# SCH_Driver_RL.net
KiCad netlist of a schematic drawn in Altium Designer
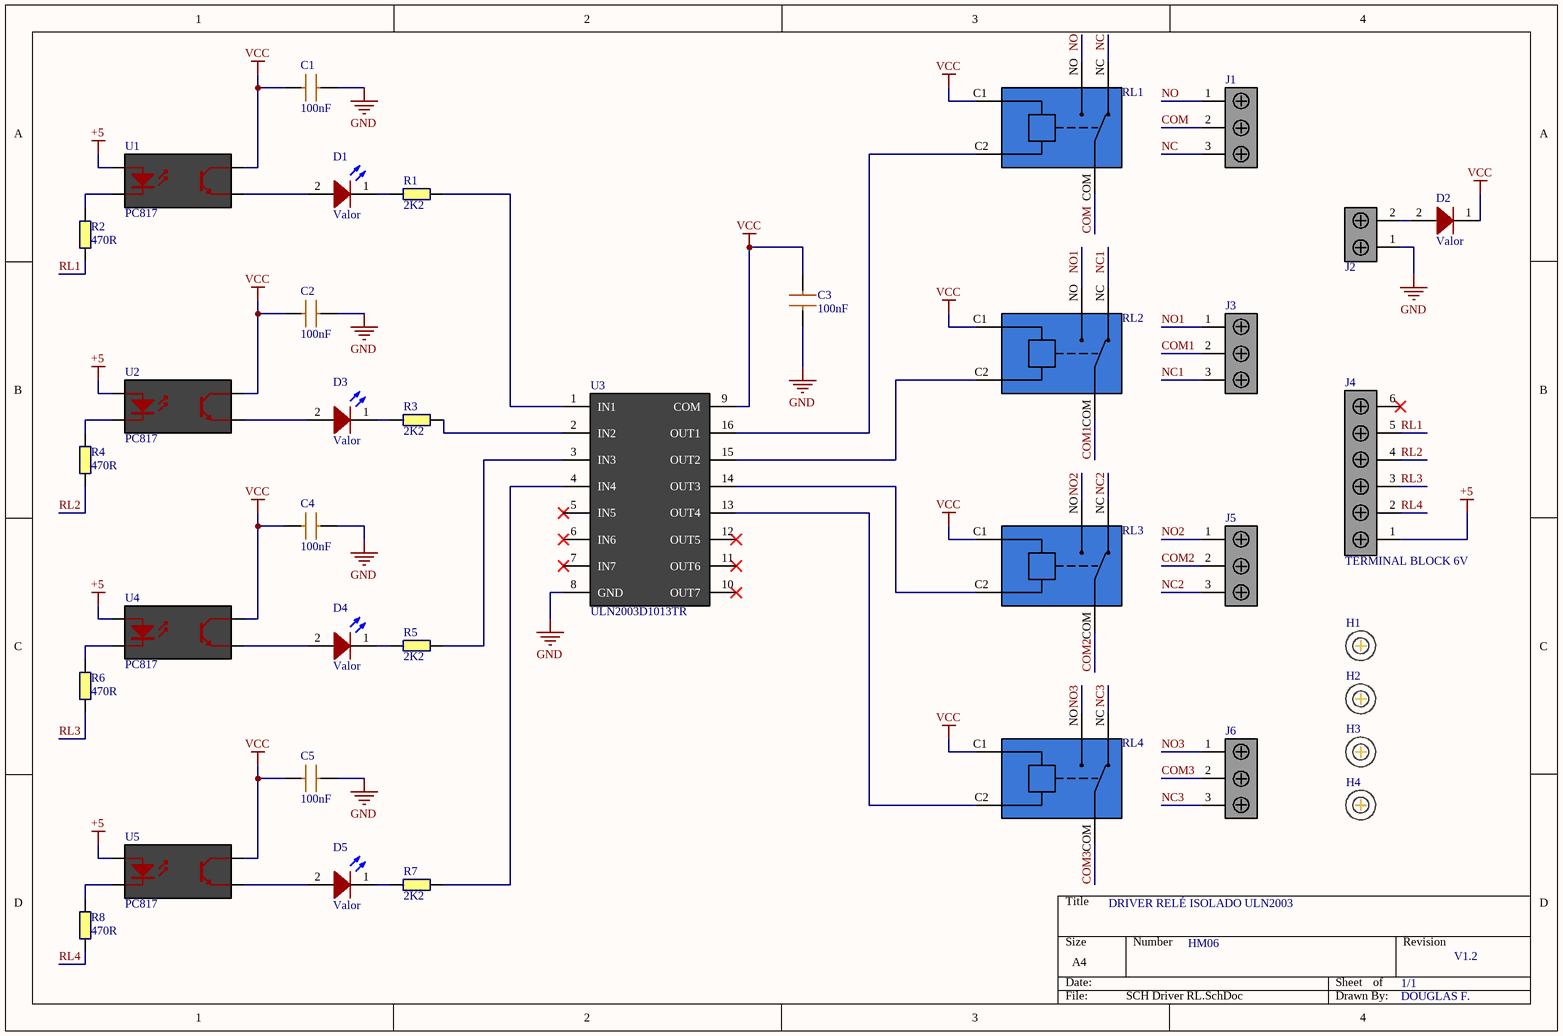
[diagram p0: SCH Driver RL.SchDoc]

(export (version "E")
  (design (tool "Eeschema 10.0.6"))
  (components
    (comp (ref "C1")
      (value "100nF")
      (footprint "RAD-0.2")
      (description "Capacitor")
      (fields (field (name "PUBLISHER") "Altium Limited"))
      (libsource (lib "Driver relé") (part "CAPACITOR"))
    )
    (comp (ref "C2")
      (value "100nF")
      (footprint "RAD-0.2")
      (description "Capacitor")
      (fields (field (name "PUBLISHER") "Altium Limited"))
      (libsource (lib "Driver relé") (part "CAPACITOR"))
    )
    (comp (ref "C3")
      (value "100nF")
      (footprint "RAD-0.2")
      (description "Capacitor")
      (fields (field (name "PUBLISHER") "Altium Limited"))
      (libsource (lib "Driver relé") (part "CAPACITOR"))
    )
    (comp (ref "C4")
      (value "100nF")
      (footprint "RAD-0.2")
      (description "Capacitor")
      (fields (field (name "PUBLISHER") "Altium Limited"))
      (libsource (lib "Driver relé") (part "CAPACITOR"))
    )
    (comp (ref "C5")
      (value "100nF")
      (footprint "RAD-0.2")
      (description "Capacitor")
      (fields (field (name "PUBLISHER") "Altium Limited"))
      (libsource (lib "Driver relé") (part "CAPACITOR"))
    )
    (comp (ref "D1")
      (value "Valor")
      (footprint "LED 3MM")
      (description "Typical RED, GREEN, YELLOW, AMBER GaAs LED")
      (fields (field (name "PUBLISHER") "Altium Limited"))
      (libsource (lib "Driver relé") (part "LED"))
    )
    (comp (ref "D2")
      (value "Valor")
      (footprint "1N4007 DO-41")
      (description "Diodo rapido")
      (fields (field (name "PUBLISHER") "Altium Limited"))
      (libsource (lib "Driver relé") (part "DIODO 1N4007"))
    )
    (comp (ref "D3")
      (value "Valor")
      (footprint "LED 3MM")
      (description "Typical RED, GREEN, YELLOW, AMBER GaAs LED")
      (fields (field (name "PUBLISHER") "Altium Limited"))
      (libsource (lib "Driver relé") (part "LED"))
    )
    (comp (ref "D4")
      (value "Valor")
      (footprint "LED 3MM")
      (description "Typical RED, GREEN, YELLOW, AMBER GaAs LED")
      (fields (field (name "PUBLISHER") "Altium Limited"))
      (libsource (lib "Driver relé") (part "LED"))
    )
    (comp (ref "D5")
      (value "Valor")
      (footprint "LED 3MM")
      (description "Typical RED, GREEN, YELLOW, AMBER GaAs LED")
      (fields (field (name "PUBLISHER") "Altium Limited"))
      (libsource (lib "Driver relé") (part "LED"))
    )
    (comp (ref "H1") (value "M3") (footprint "Parafuso M3") (libsource (lib "Driver relé") (part "Furo M3")))
    (comp (ref "H2") (value "M3") (footprint "Parafuso M3") (libsource (lib "Driver relé") (part "Furo M3")))
    (comp (ref "H3") (value "M3") (footprint "Parafuso M3") (libsource (lib "Driver relé") (part "Furo M3")))
    (comp (ref "H4") (value "M3") (footprint "Parafuso M3") (libsource (lib "Driver relé") (part "Furo M3")))
    (comp (ref "J1")
      (value "Conector 2v Phoenix")
      (footprint "Terminal block 5mm 3V")
      (description "Block, Terminal; 6 A; 63 V; 5 mm; 26 to 20 AWG; 3; Screw; Soldering; 1.5 kV")
      (fields
        (field (name "MANUFACTURER") "Phoenix Contact")
        (field (name "MANUFACTURER PART NUMBER") "1725656")
      )
      (libsource (lib "Driver relé") (part "TERMINAL BLOCK 3V"))
    )
    (comp (ref "J2")
      (value "Conector 2v Phoenix")
      (footprint "Terminal block 5mm 2V")
      (description "Block, Terminal; 6 A; 63 V; 5 mm; 26 to 20 AWG; 2; Screw; Soldering; 1.5 kV")
      (fields
        (field (name "MANUFACTURER") "Phoenix Contact")
        (field (name "MANUFACTURER PART NUMBER") "1725656")
      )
      (libsource (lib "Driver relé") (part "TERMINAL BLOCK 2V"))
    )
    (comp (ref "J3")
      (value "Conector 2v Phoenix")
      (footprint "Terminal block 5mm 3V")
      (description "Block, Terminal; 6 A; 63 V; 5 mm; 26 to 20 AWG; 3; Screw; Soldering; 1.5 kV")
      (fields
        (field (name "MANUFACTURER") "Phoenix Contact")
        (field (name "MANUFACTURER PART NUMBER") "1725656")
      )
      (libsource (lib "Driver relé") (part "TERMINAL BLOCK 3V"))
    )
    (comp (ref "J4")
      (value "TERMINAL BLOCK 6V")
      (footprint "Terminal block 5mm 6V")
      (description "Block, Terminal; 6 A; 63 V; 5 mm; 26 to 20 AWG; 6 Screw; Soldering; 1.5 kV")
      (libsource (lib "Driver relé") (part "TERMINAL BLOCK 6V"))
    )
    (comp (ref "J5")
      (value "Conector 2v Phoenix")
      (footprint "Terminal block 5mm 3V")
      (description "Block, Terminal; 6 A; 63 V; 5 mm; 26 to 20 AWG; 3; Screw; Soldering; 1.5 kV")
      (fields
        (field (name "MANUFACTURER") "Phoenix Contact")
        (field (name "MANUFACTURER PART NUMBER") "1725656")
      )
      (libsource (lib "Driver relé") (part "TERMINAL BLOCK 3V"))
    )
    (comp (ref "J6")
      (value "Conector 2v Phoenix")
      (footprint "Terminal block 5mm 3V")
      (description "Block, Terminal; 6 A; 63 V; 5 mm; 26 to 20 AWG; 3; Screw; Soldering; 1.5 kV")
      (fields
        (field (name "MANUFACTURER") "Phoenix Contact")
        (field (name "MANUFACTURER PART NUMBER") "1725656")
      )
      (libsource (lib "Driver relé") (part "TERMINAL BLOCK 3V"))
    )
    (comp (ref "R1")
      (value "2K2")
      (footprint "RES 1/4 PTH")
      (description "Resistor")
      (fields (field (name "PUBLISHER") "Altium Limited"))
      (libsource (lib "") (part "RESISTOR 1/4W_1"))
    )
    (comp (ref "R2")
      (value "470R")
      (footprint "RES 1/4 PTH")
      (description "Resistor")
      (fields (field (name "PUBLISHER") "Altium Limited"))
      (libsource (lib "Driver relé") (part "RESISTOR 1/4W"))
    )
    (comp (ref "R3")
      (value "2K2")
      (footprint "RES 1/4 PTH")
      (description "Resistor")
      (fields (field (name "PUBLISHER") "Altium Limited"))
      (libsource (lib "") (part "RESISTOR 1/4W_1"))
    )
    (comp (ref "R4")
      (value "470R")
      (footprint "RES 1/4 PTH")
      (description "Resistor")
      (fields (field (name "PUBLISHER") "Altium Limited"))
      (libsource (lib "Driver relé") (part "RESISTOR 1/4W"))
    )
    (comp (ref "R5")
      (value "2K2")
      (footprint "RES 1/4 PTH")
      (description "Resistor")
      (fields (field (name "PUBLISHER") "Altium Limited"))
      (libsource (lib "") (part "RESISTOR 1/4W_1"))
    )
    (comp (ref "R6")
      (value "470R")
      (footprint "RES 1/4 PTH")
      (description "Resistor")
      (fields (field (name "PUBLISHER") "Altium Limited"))
      (libsource (lib "Driver relé") (part "RESISTOR 1/4W"))
    )
    (comp (ref "R7")
      (value "2K2")
      (footprint "RES 1/4 PTH")
      (description "Resistor")
      (fields (field (name "PUBLISHER") "Altium Limited"))
      (libsource (lib "") (part "RESISTOR 1/4W_1"))
    )
    (comp (ref "R8")
      (value "470R")
      (footprint "RES 1/4 PTH")
      (description "Resistor")
      (fields (field (name "PUBLISHER") "Altium Limited"))
      (libsource (lib "Driver relé") (part "RESISTOR 1/4W"))
    )
    (comp (ref "RL1")
      (value "Relé 12v 5p")
      (footprint "RELAY")
      (libsource (lib "Driver relé") (part "Relé 12v 5p"))
    )
    (comp (ref "RL2")
      (value "Relé 12v 5p")
      (footprint "RELAY")
      (libsource (lib "Driver relé") (part "Relé 12v 5p"))
    )
    (comp (ref "RL3")
      (value "Relé 12v 5p")
      (footprint "RELAY")
      (libsource (lib "Driver relé") (part "Relé 12v 5p"))
    )
    (comp (ref "RL4")
      (value "Relé 12v 5p")
      (footprint "RELAY")
      (libsource (lib "Driver relé") (part "Relé 12v 5p"))
    )
    (comp (ref "U1") (value "PC817") (footprint "PC817 DIP-4") (libsource (lib "Driver relé") (part "PC817")))
    (comp (ref "U2") (value "PC817") (footprint "PC817 DIP-4") (libsource (lib "Driver relé") (part "PC817")))
    (comp (ref "U3")
      (value "ULN2003D1013TR")
      (footprint "PDIP-16")
      (description "ULN Series 50V 500 mA High Voltage High Current Seven Darlington Array - SOIC-16")
      (fields (field (name "MANUFACTURER") "STMicroelectronics"))
      (libsource (lib "Driver relé") (part "ULN2003D1013TR"))
    )
    (comp (ref "U4") (value "PC817") (footprint "PC817 DIP-4") (libsource (lib "Driver relé") (part "PC817")))
    (comp (ref "U5") (value "PC817") (footprint "PC817 DIP-4") (libsource (lib "Driver relé") (part "PC817")))
  )
  (nets
    (net (code "1") (name "+5") (class "Default")
      (node (ref "J4") (pin "1") (pinfunction "1_1") (pintype "passive"))
      (node (ref "U1") (pin "1") (pinfunction "A_1") (pintype "passive"))
      (node (ref "U2") (pin "1") (pinfunction "A_1") (pintype "passive"))
      (node (ref "U4") (pin "1") (pinfunction "A_1") (pintype "passive"))
      (node (ref "U5") (pin "1") (pinfunction "A_1") (pintype "passive"))
    )
    (net (code "2") (name "/COM") (class "Default")
      (node (ref "J1") (pin "2") (pinfunction "2_2") (pintype "passive"))
      (node (ref "RL1") (pin "COM") (pinfunction "COM_COM") (pintype "passive"))
    )
    (net (code "3") (name "/COM1") (class "Default")
      (node (ref "J3") (pin "2") (pinfunction "2_2") (pintype "passive"))
      (node (ref "RL2") (pin "COM") (pinfunction "COM_COM") (pintype "passive"))
    )
    (net (code "4") (name "/COM2") (class "Default")
      (node (ref "J5") (pin "2") (pinfunction "2_2") (pintype "passive"))
      (node (ref "RL3") (pin "COM") (pinfunction "COM_COM") (pintype "passive"))
    )
    (net (code "5") (name "/COM3") (class "Default")
      (node (ref "J6") (pin "2") (pinfunction "2_2") (pintype "passive"))
      (node (ref "RL4") (pin "COM") (pinfunction "COM_COM") (pintype "passive"))
    )
    (net (code "6") (name "/NC") (class "Default")
      (node (ref "J1") (pin "3") (pinfunction "3_3") (pintype "passive"))
      (node (ref "RL1") (pin "NC") (pinfunction "NC_NC") (pintype "passive"))
    )
    (net (code "7") (name "/NC1") (class "Default")
      (node (ref "J3") (pin "3") (pinfunction "3_3") (pintype "passive"))
      (node (ref "RL2") (pin "NC") (pinfunction "NC_NC") (pintype "passive"))
    )
    (net (code "8") (name "/NC2") (class "Default")
      (node (ref "J5") (pin "3") (pinfunction "3_3") (pintype "passive"))
      (node (ref "RL3") (pin "NC") (pinfunction "NC_NC") (pintype "passive"))
    )
    (net (code "9") (name "/NC3") (class "Default")
      (node (ref "J6") (pin "3") (pinfunction "3_3") (pintype "passive"))
      (node (ref "RL4") (pin "NC") (pinfunction "NC_NC") (pintype "passive"))
    )
    (net (code "10") (name "/NO") (class "Default")
      (node (ref "J1") (pin "1") (pinfunction "1_1") (pintype "passive"))
      (node (ref "RL1") (pin "NO") (pinfunction "NO_NO") (pintype "passive"))
    )
    (net (code "11") (name "/NO1") (class "Default")
      (node (ref "J3") (pin "1") (pinfunction "1_1") (pintype "passive"))
      (node (ref "RL2") (pin "NO") (pinfunction "NO_NO") (pintype "passive"))
    )
    (net (code "12") (name "/NO2") (class "Default")
      (node (ref "J5") (pin "1") (pinfunction "1_1") (pintype "passive"))
      (node (ref "RL3") (pin "NO") (pinfunction "NO_NO") (pintype "passive"))
    )
    (net (code "13") (name "/NO3") (class "Default")
      (node (ref "J6") (pin "1") (pinfunction "1_1") (pintype "passive"))
      (node (ref "RL4") (pin "NO") (pinfunction "NO_NO") (pintype "passive"))
    )
    (net (code "14") (name "/RL1") (class "Default")
      (node (ref "J4") (pin "5") (pinfunction "5_5") (pintype "passive"))
      (node (ref "R2") (pin "1") (pinfunction "1_1") (pintype "passive"))
    )
    (net (code "15") (name "/RL2") (class "Default")
      (node (ref "J4") (pin "4") (pinfunction "4_4") (pintype "passive"))
      (node (ref "R4") (pin "1") (pinfunction "1_1") (pintype "passive"))
    )
    (net (code "16") (name "/RL3") (class "Default")
      (node (ref "J4") (pin "3") (pinfunction "3_3") (pintype "passive"))
      (node (ref "R6") (pin "1") (pinfunction "1_1") (pintype "passive"))
    )
    (net (code "17") (name "/RL4") (class "Default")
      (node (ref "J4") (pin "2") (pinfunction "2_2") (pintype "passive"))
      (node (ref "R8") (pin "1") (pinfunction "1_1") (pintype "passive"))
    )
    (net (code "18") (name "GND") (class "Default")
      (node (ref "C1") (pin "1") (pinfunction "1_1") (pintype "passive"))
      (node (ref "C2") (pin "1") (pinfunction "1_1") (pintype "passive"))
      (node (ref "C3") (pin "1") (pinfunction "1_1") (pintype "passive"))
      (node (ref "C4") (pin "1") (pinfunction "1_1") (pintype "passive"))
      (node (ref "C5") (pin "1") (pinfunction "1_1") (pintype "passive"))
      (node (ref "J2") (pin "1") (pinfunction "1_1") (pintype "passive"))
      (node (ref "U3") (pin "8") (pinfunction "GND_8") (pintype "passive"))
    )
    (net (code "19") (name "Net-(D1-1)") (class "Default")
      (node (ref "D1") (pin "2") (pinfunction "1_2") (pintype "passive"))
      (node (ref "U1") (pin "3") (pinfunction "E_3") (pintype "passive"))
    )
    (net (code "20") (name "Net-(D1-2)") (class "Default")
      (node (ref "D1") (pin "1") (pinfunction "2_1") (pintype "passive"))
      (node (ref "R1") (pin "1") (pinfunction "1_1") (pintype "passive"))
    )
    (net (code "21") (name "Net-(D2-Pad2)") (class "Default")
      (node (ref "D2") (pin "2") (pinfunction "2_2") (pintype "passive"))
      (node (ref "J2") (pin "2") (pinfunction "2_2") (pintype "passive"))
    )
    (net (code "22") (name "Net-(D3-1)") (class "Default")
      (node (ref "D3") (pin "2") (pinfunction "1_2") (pintype "passive"))
      (node (ref "U2") (pin "3") (pinfunction "E_3") (pintype "passive"))
    )
    (net (code "23") (name "Net-(D3-2)") (class "Default")
      (node (ref "D3") (pin "1") (pinfunction "2_1") (pintype "passive"))
      (node (ref "R3") (pin "1") (pinfunction "1_1") (pintype "passive"))
    )
    (net (code "24") (name "Net-(D4-1)") (class "Default")
      (node (ref "D4") (pin "2") (pinfunction "1_2") (pintype "passive"))
      (node (ref "U4") (pin "3") (pinfunction "E_3") (pintype "passive"))
    )
    (net (code "25") (name "Net-(D4-2)") (class "Default")
      (node (ref "D4") (pin "1") (pinfunction "2_1") (pintype "passive"))
      (node (ref "R5") (pin "1") (pinfunction "1_1") (pintype "passive"))
    )
    (net (code "26") (name "Net-(D5-1)") (class "Default")
      (node (ref "D5") (pin "2") (pinfunction "1_2") (pintype "passive"))
      (node (ref "U5") (pin "3") (pinfunction "E_3") (pintype "passive"))
    )
    (net (code "27") (name "Net-(D5-2)") (class "Default")
      (node (ref "D5") (pin "1") (pinfunction "2_1") (pintype "passive"))
      (node (ref "R7") (pin "1") (pinfunction "1_1") (pintype "passive"))
    )
    (net (code "28") (name "Net-(RL1-COIL_2)") (class "Default")
      (node (ref "RL1") (pin "C2") (pinfunction "COIL_2_C2") (pintype "passive"))
      (node (ref "U3") (pin "16") (pinfunction "OUT1_16") (pintype "passive"))
    )
    (net (code "29") (name "Net-(RL2-COIL_2)") (class "Default")
      (node (ref "RL2") (pin "C2") (pinfunction "COIL_2_C2") (pintype "passive"))
      (node (ref "U3") (pin "15") (pinfunction "OUT2_15") (pintype "passive"))
    )
    (net (code "30") (name "Net-(RL3-COIL_2)") (class "Default")
      (node (ref "RL3") (pin "C2") (pinfunction "COIL_2_C2") (pintype "passive"))
      (node (ref "U3") (pin "14") (pinfunction "OUT3_14") (pintype "passive"))
    )
    (net (code "31") (name "Net-(RL4-COIL_2)") (class "Default")
      (node (ref "RL4") (pin "C2") (pinfunction "COIL_2_C2") (pintype "passive"))
      (node (ref "U3") (pin "13") (pinfunction "OUT4_13") (pintype "passive"))
    )
    (net (code "32") (name "Net-(U1-K)") (class "Default")
      (node (ref "R2") (pin "2") (pinfunction "2_2") (pintype "passive"))
      (node (ref "U1") (pin "2") (pinfunction "K_2") (pintype "passive"))
    )
    (net (code "33") (name "Net-(U2-K)") (class "Default")
      (node (ref "R4") (pin "2") (pinfunction "2_2") (pintype "passive"))
      (node (ref "U2") (pin "2") (pinfunction "K_2") (pintype "passive"))
    )
    (net (code "34") (name "Net-(U3-IN1)") (class "Default")
      (node (ref "R1") (pin "2") (pinfunction "2_2") (pintype "passive"))
      (node (ref "U3") (pin "1") (pinfunction "IN1_1") (pintype "passive"))
    )
    (net (code "35") (name "Net-(U3-IN2)") (class "Default")
      (node (ref "R3") (pin "2") (pinfunction "2_2") (pintype "passive"))
      (node (ref "U3") (pin "2") (pinfunction "IN2_2") (pintype "passive"))
    )
    (net (code "36") (name "Net-(U3-IN3)") (class "Default")
      (node (ref "R5") (pin "2") (pinfunction "2_2") (pintype "passive"))
      (node (ref "U3") (pin "3") (pinfunction "IN3_3") (pintype "passive"))
    )
    (net (code "37") (name "Net-(U3-IN4)") (class "Default")
      (node (ref "R7") (pin "2") (pinfunction "2_2") (pintype "passive"))
      (node (ref "U3") (pin "4") (pinfunction "IN4_4") (pintype "passive"))
    )
    (net (code "38") (name "Net-(U4-K)") (class "Default")
      (node (ref "R6") (pin "2") (pinfunction "2_2") (pintype "passive"))
      (node (ref "U4") (pin "2") (pinfunction "K_2") (pintype "passive"))
    )
    (net (code "39") (name "Net-(U5-K)") (class "Default")
      (node (ref "R8") (pin "2") (pinfunction "2_2") (pintype "passive"))
      (node (ref "U5") (pin "2") (pinfunction "K_2") (pintype "passive"))
    )
    (net (code "40") (name "VCC") (class "Default")
      (node (ref "C1") (pin "2") (pinfunction "2_2") (pintype "passive"))
      (node (ref "C2") (pin "2") (pinfunction "2_2") (pintype "passive"))
      (node (ref "C3") (pin "2") (pinfunction "2_2") (pintype "passive"))
      (node (ref "C4") (pin "2") (pinfunction "2_2") (pintype "passive"))
      (node (ref "C5") (pin "2") (pinfunction "2_2") (pintype "passive"))
      (node (ref "D2") (pin "1") (pinfunction "1_1") (pintype "passive"))
      (node (ref "RL1") (pin "C1") (pinfunction "COIL_1_C1") (pintype "passive"))
      (node (ref "RL2") (pin "C1") (pinfunction "COIL_1_C1") (pintype "passive"))
      (node (ref "RL3") (pin "C1") (pinfunction "COIL_1_C1") (pintype "passive"))
      (node (ref "RL4") (pin "C1") (pinfunction "COIL_1_C1") (pintype "passive"))
      (node (ref "U1") (pin "4") (pinfunction "C_4") (pintype "passive"))
      (node (ref "U2") (pin "4") (pinfunction "C_4") (pintype "passive"))
      (node (ref "U3") (pin "9") (pinfunction "COM_9") (pintype "passive"))
      (node (ref "U4") (pin "4") (pinfunction "C_4") (pintype "passive"))
      (node (ref "U5") (pin "4") (pinfunction "C_4") (pintype "passive"))
    )
    (net (code "41") (name "unconnected-(J4-Pad6)") (class "Default")
      (node (ref "J4") (pin "6") (pinfunction "6_6") (pintype "passive+no_connect"))
    )
    (net (code "42") (name "unconnected-(U3-IN5-Pad5)") (class "Default")
      (node (ref "U3") (pin "5") (pinfunction "IN5_5") (pintype "passive+no_connect"))
    )
    (net (code "43") (name "unconnected-(U3-IN6-Pad6)") (class "Default")
      (node (ref "U3") (pin "6") (pinfunction "IN6_6") (pintype "passive+no_connect"))
    )
    (net (code "44") (name "unconnected-(U3-IN7-Pad7)") (class "Default")
      (node (ref "U3") (pin "7") (pinfunction "IN7_7") (pintype "passive+no_connect"))
    )
    (net (code "45") (name "unconnected-(U3-OUT5-Pad12)") (class "Default")
      (node (ref "U3") (pin "12") (pinfunction "OUT5_12") (pintype "passive+no_connect"))
    )
    (net (code "46") (name "unconnected-(U3-OUT6-Pad11)") (class "Default")
      (node (ref "U3") (pin "11") (pinfunction "OUT6_11") (pintype "passive+no_connect"))
    )
    (net (code "47") (name "unconnected-(U3-OUT7-Pad10)") (class "Default")
      (node (ref "U3") (pin "10") (pinfunction "OUT7_10") (pintype "passive+no_connect"))
    )
  )
)
